# multiplexor.net
KiCad netlist of a schematic drawn in EAGLE
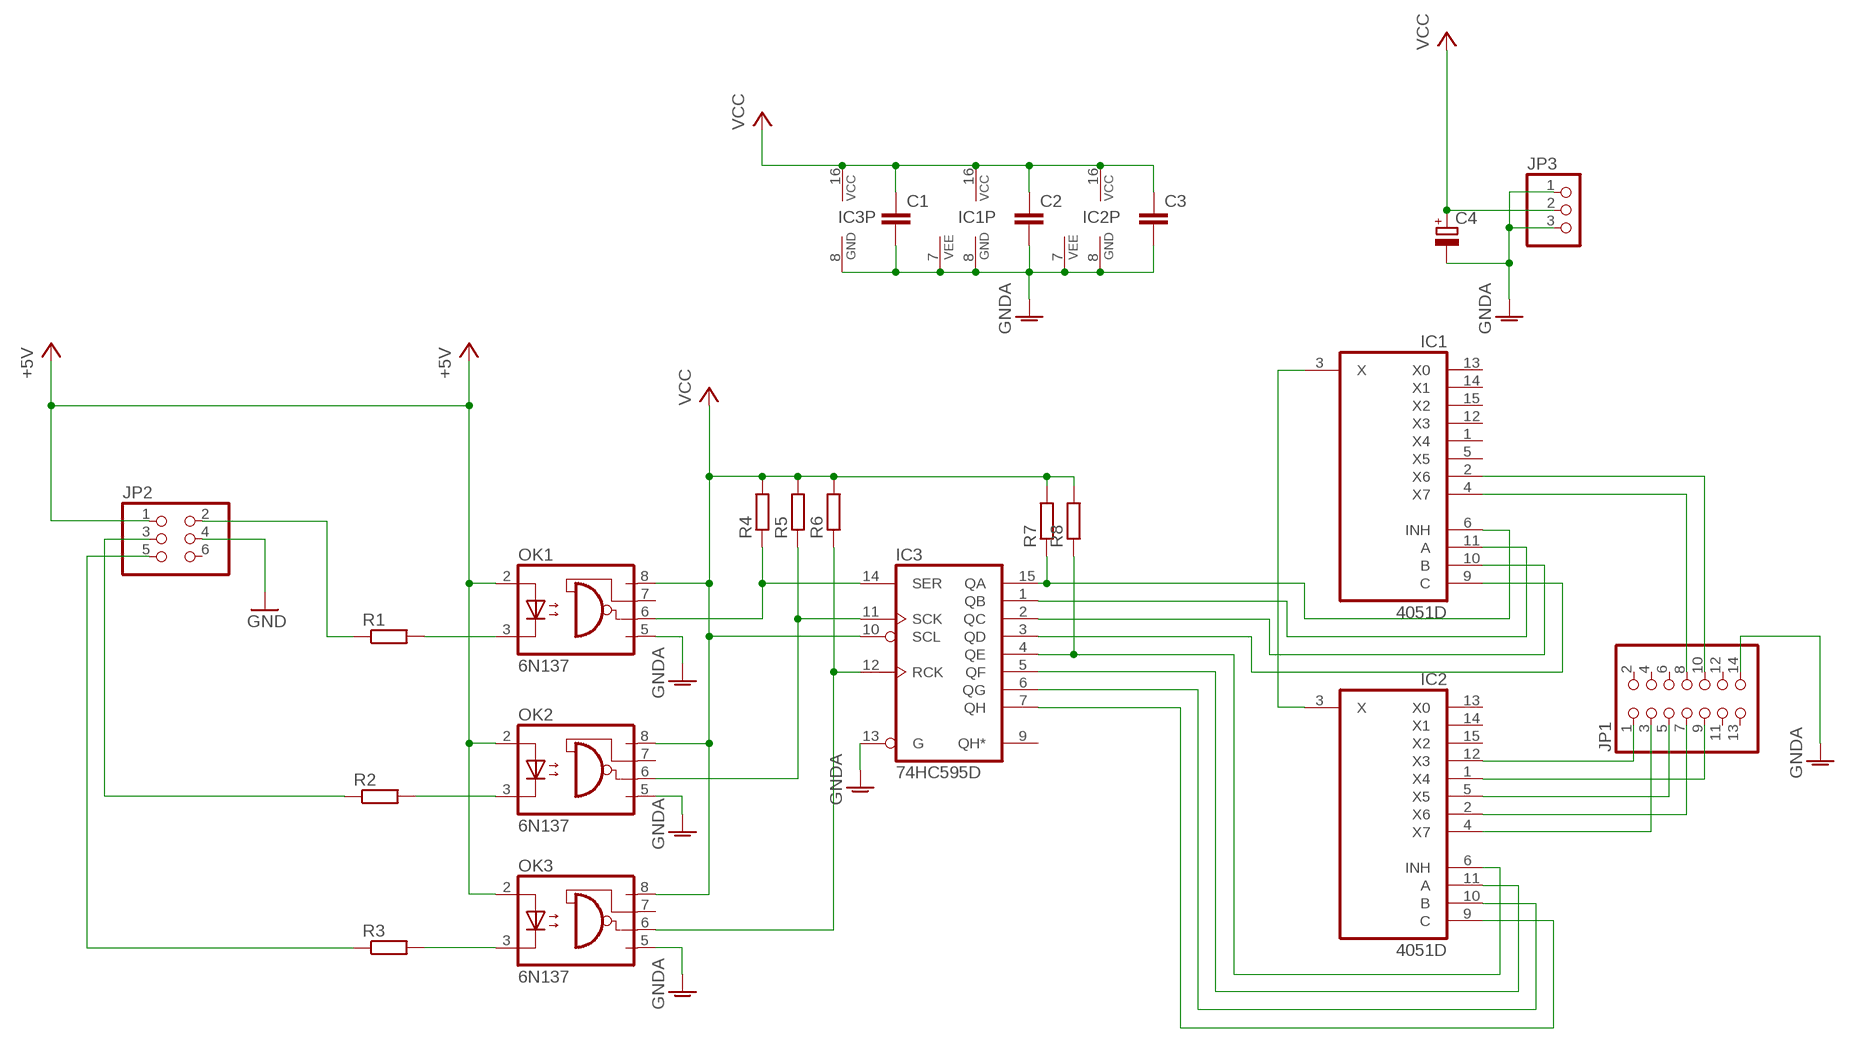
[diagram p0: schematic, sheet 1]

(export (version "E")
  (design (tool "Eeschema 10.0.6"))
  (components
    (comp (ref "C1")
      (value "C-EUC1206K")
      (footprint "eagle-import:C1206K")
      (libsource (lib "eagle-import") (part "C-EUC1206K"))
    )
    (comp (ref "C2")
      (value "C-EUC1206K")
      (footprint "eagle-import:C1206K")
      (libsource (lib "eagle-import") (part "C-EUC1206K"))
    )
    (comp (ref "C3")
      (value "C-EUC1206K")
      (footprint "eagle-import:C1206K")
      (libsource (lib "eagle-import") (part "C-EUC1206K"))
    )
    (comp (ref "C4")
      (value "CPOL-EUE2.5-6")
      (footprint "eagle-import:E2,5-6")
      (libsource (lib "eagle-import") (part "CPOL-EUE2.5-6"))
    )
    (comp (ref "IC1")
      (value "4051D")
      (footprint "eagle-import:SO16")
      (libsource (lib "eagle-import") (part "4051D"))
    )
    (comp (ref "IC2")
      (value "4051D")
      (footprint "eagle-import:SO16")
      (libsource (lib "eagle-import") (part "4051D"))
    )
    (comp (ref "IC3")
      (value "74HC595D")
      (footprint "eagle-import:SO16")
      (libsource (lib "eagle-import") (part "74595DHC"))
    )
    (comp (ref "JP1")
      (value "PINHD-2X7")
      (footprint "eagle-import:2X07")
      (libsource (lib "eagle-import") (part "PINHD-2X7"))
    )
    (comp (ref "JP2")
      (value "PINHD-2X3")
      (footprint "eagle-import:2X03")
      (libsource (lib "eagle-import") (part "PINHD-2X3"))
    )
    (comp (ref "JP3")
      (value "PINHD-1X3")
      (footprint "eagle-import:1X03")
      (libsource (lib "eagle-import") (part "PINHD-1X3"))
    )
    (comp (ref "OK1")
      (value "6N137")
      (footprint "eagle-import:DIL08")
      (libsource (lib "eagle-import") (part "6N137"))
    )
    (comp (ref "OK2")
      (value "6N137")
      (footprint "eagle-import:DIL08")
      (libsource (lib "eagle-import") (part "6N137"))
    )
    (comp (ref "OK3")
      (value "6N137")
      (footprint "eagle-import:DIL08")
      (libsource (lib "eagle-import") (part "6N137"))
    )
    (comp (ref "R1")
      (value "R-EU_R1206")
      (footprint "eagle-import:R1206")
      (libsource (lib "eagle-import") (part "R-EU_R1206"))
    )
    (comp (ref "R2")
      (value "R-EU_R1206")
      (footprint "eagle-import:R1206")
      (libsource (lib "eagle-import") (part "R-EU_R1206"))
    )
    (comp (ref "R3")
      (value "R-EU_R1206")
      (footprint "eagle-import:R1206")
      (libsource (lib "eagle-import") (part "R-EU_R1206"))
    )
    (comp (ref "R4")
      (value "R-EU_R1206")
      (footprint "eagle-import:R1206")
      (libsource (lib "eagle-import") (part "R-EU_R1206"))
    )
    (comp (ref "R5")
      (value "R-EU_R1206")
      (footprint "eagle-import:R1206")
      (libsource (lib "eagle-import") (part "R-EU_R1206"))
    )
    (comp (ref "R6")
      (value "R-EU_R1206")
      (footprint "eagle-import:R1206")
      (libsource (lib "eagle-import") (part "R-EU_R1206"))
    )
    (comp (ref "R7")
      (value "R-EU_R1206")
      (footprint "eagle-import:R1206")
      (libsource (lib "eagle-import") (part "R-EU_R1206"))
    )
    (comp (ref "R8")
      (value "R-EU_R1206")
      (footprint "eagle-import:R1206")
      (libsource (lib "eagle-import") (part "R-EU_R1206"))
    )
  )
  (nets
    (net (code "1") (name "+5V") (class "Default")
      (node (ref "JP2") (pin "1") (pinfunction "1_1") (pintype "passive"))
      (node (ref "OK1") (pin "2") (pinfunction "A_2") (pintype "passive"))
      (node (ref "OK2") (pin "2") (pinfunction "A_2") (pintype "passive"))
      (node (ref "OK3") (pin "2") (pinfunction "A_2") (pintype "passive"))
    )
    (net (code "2") (name "GND") (class "Default")
      (node (ref "JP2") (pin "4") (pinfunction "4_4") (pintype "passive"))
    )
    (net (code "3") (name "GNDA") (class "Default")
      (node (ref "C1") (pin "2") (pinfunction "2_2") (pintype "passive"))
      (node (ref "C2") (pin "2") (pinfunction "2_2") (pintype "passive"))
      (node (ref "C3") (pin "2") (pinfunction "2_2") (pintype "passive"))
      (node (ref "C4") (pin "-") (pinfunction "-_-") (pintype "passive"))
      (node (ref "IC1") (pin "7") (pinfunction "VEE_7") (pintype "power_in"))
      (node (ref "IC1") (pin "8") (pinfunction "GND_8") (pintype "power_in"))
      (node (ref "IC2") (pin "7") (pinfunction "VEE_7") (pintype "power_in"))
      (node (ref "IC2") (pin "8") (pinfunction "GND_8") (pintype "power_in"))
      (node (ref "IC3") (pin "13") (pinfunction "G_13") (pintype "input"))
      (node (ref "IC3") (pin "8") (pinfunction "GND_8") (pintype "power_in"))
      (node (ref "JP1") (pin "14") (pinfunction "14_14") (pintype "passive"))
      (node (ref "JP3") (pin "1") (pinfunction "1_1") (pintype "passive"))
      (node (ref "JP3") (pin "3") (pinfunction "3_3") (pintype "passive"))
      (node (ref "OK1") (pin "5") (pinfunction "GND_5") (pintype "passive"))
      (node (ref "OK2") (pin "5") (pinfunction "GND_5") (pintype "passive"))
      (node (ref "OK3") (pin "5") (pinfunction "GND_5") (pintype "passive"))
    )
    (net (code "4") (name "Net-(IC1A-A)") (class "Default")
      (node (ref "IC1") (pin "11") (pinfunction "A_11") (pintype "input"))
      (node (ref "IC3") (pin "1") (pinfunction "QB_1") (pintype "tri_state"))
    )
    (net (code "5") (name "Net-(IC1A-B)") (class "Default")
      (node (ref "IC1") (pin "10") (pinfunction "B_10") (pintype "input"))
      (node (ref "IC3") (pin "2") (pinfunction "QC_2") (pintype "tri_state"))
    )
    (net (code "6") (name "Net-(IC1A-C)") (class "Default")
      (node (ref "IC1") (pin "9") (pinfunction "C_9") (pintype "input"))
      (node (ref "IC3") (pin "3") (pinfunction "QD_3") (pintype "tri_state"))
    )
    (net (code "7") (name "Net-(IC1A-INH)") (class "Default")
      (node (ref "IC1") (pin "6") (pinfunction "INH_6") (pintype "input"))
      (node (ref "IC3") (pin "15") (pinfunction "QA_15") (pintype "tri_state"))
      (node (ref "R7") (pin "1") (pinfunction "1_1") (pintype "passive"))
    )
    (net (code "8") (name "Net-(IC1A-X)") (class "Default")
      (node (ref "IC1") (pin "3") (pinfunction "X_3") (pintype "bidirectional"))
      (node (ref "IC2") (pin "3") (pinfunction "X_3") (pintype "bidirectional"))
    )
    (net (code "9") (name "Net-(IC1A-X6)") (class "Default")
      (node (ref "IC1") (pin "2") (pinfunction "X6_2") (pintype "bidirectional"))
      (node (ref "JP1") (pin "10") (pinfunction "10_10") (pintype "passive"))
    )
    (net (code "10") (name "Net-(IC1A-X7)") (class "Default")
      (node (ref "IC1") (pin "4") (pinfunction "X7_4") (pintype "bidirectional"))
      (node (ref "JP1") (pin "8") (pinfunction "8_8") (pintype "passive"))
    )
    (net (code "11") (name "Net-(IC2A-A)") (class "Default")
      (node (ref "IC2") (pin "11") (pinfunction "A_11") (pintype "input"))
      (node (ref "IC3") (pin "5") (pinfunction "QF_5") (pintype "tri_state"))
    )
    (net (code "12") (name "Net-(IC2A-B)") (class "Default")
      (node (ref "IC2") (pin "10") (pinfunction "B_10") (pintype "input"))
      (node (ref "IC3") (pin "6") (pinfunction "QG_6") (pintype "tri_state"))
    )
    (net (code "13") (name "Net-(IC2A-C)") (class "Default")
      (node (ref "IC2") (pin "9") (pinfunction "C_9") (pintype "input"))
      (node (ref "IC3") (pin "7") (pinfunction "QH_7") (pintype "tri_state"))
    )
    (net (code "14") (name "Net-(IC2A-INH)") (class "Default")
      (node (ref "IC2") (pin "6") (pinfunction "INH_6") (pintype "input"))
      (node (ref "IC3") (pin "4") (pinfunction "QE_4") (pintype "tri_state"))
      (node (ref "R8") (pin "1") (pinfunction "1_1") (pintype "passive"))
    )
    (net (code "15") (name "Net-(IC2A-X3)") (class "Default")
      (node (ref "IC2") (pin "12") (pinfunction "X3_12") (pintype "bidirectional"))
      (node (ref "JP1") (pin "1") (pinfunction "1_1") (pintype "passive"))
    )
    (net (code "16") (name "Net-(IC2A-X4)") (class "Default")
      (node (ref "IC2") (pin "1") (pinfunction "X4_1") (pintype "bidirectional"))
      (node (ref "JP1") (pin "9") (pinfunction "9_9") (pintype "passive"))
    )
    (net (code "17") (name "Net-(IC2A-X5)") (class "Default")
      (node (ref "IC2") (pin "5") (pinfunction "X5_5") (pintype "bidirectional"))
      (node (ref "JP1") (pin "5") (pinfunction "5_5") (pintype "passive"))
    )
    (net (code "18") (name "Net-(IC2A-X6)") (class "Default")
      (node (ref "IC2") (pin "2") (pinfunction "X6_2") (pintype "bidirectional"))
      (node (ref "JP1") (pin "7") (pinfunction "7_7") (pintype "passive"))
    )
    (net (code "19") (name "Net-(IC2A-X7)") (class "Default")
      (node (ref "IC2") (pin "4") (pinfunction "X7_4") (pintype "bidirectional"))
      (node (ref "JP1") (pin "3") (pinfunction "3_3") (pintype "passive"))
    )
    (net (code "20") (name "Net-(IC3A-RCK)") (class "Default")
      (node (ref "IC3") (pin "12") (pinfunction "RCK_12") (pintype "input"))
      (node (ref "OK3") (pin "6") (pinfunction "VO_6") (pintype "passive"))
      (node (ref "R6") (pin "1") (pinfunction "1_1") (pintype "passive"))
    )
    (net (code "21") (name "Net-(IC3A-SCK)") (class "Default")
      (node (ref "IC3") (pin "11") (pinfunction "SCK_11") (pintype "input"))
      (node (ref "OK2") (pin "6") (pinfunction "VO_6") (pintype "passive"))
      (node (ref "R5") (pin "1") (pinfunction "1_1") (pintype "passive"))
    )
    (net (code "22") (name "Net-(IC3A-SER)") (class "Default")
      (node (ref "IC3") (pin "14") (pinfunction "SER_14") (pintype "input"))
      (node (ref "OK1") (pin "6") (pinfunction "VO_6") (pintype "passive"))
      (node (ref "R4") (pin "1") (pinfunction "1_1") (pintype "passive"))
    )
    (net (code "23") (name "Net-(JP2-Pad2)") (class "Default")
      (node (ref "JP2") (pin "2") (pinfunction "2_2") (pintype "passive"))
      (node (ref "R1") (pin "1") (pinfunction "1_1") (pintype "passive"))
    )
    (net (code "24") (name "Net-(JP2-Pad3)") (class "Default")
      (node (ref "JP2") (pin "3") (pinfunction "3_3") (pintype "passive"))
      (node (ref "R2") (pin "1") (pinfunction "1_1") (pintype "passive"))
    )
    (net (code "25") (name "Net-(JP2-Pad5)") (class "Default")
      (node (ref "JP2") (pin "5") (pinfunction "5_5") (pintype "passive"))
      (node (ref "R3") (pin "1") (pinfunction "1_1") (pintype "passive"))
    )
    (net (code "26") (name "Net-(OK1-C)") (class "Default")
      (node (ref "OK1") (pin "3") (pinfunction "C_3") (pintype "passive"))
      (node (ref "R1") (pin "2") (pinfunction "2_2") (pintype "passive"))
    )
    (net (code "27") (name "Net-(OK2-C)") (class "Default")
      (node (ref "OK2") (pin "3") (pinfunction "C_3") (pintype "passive"))
      (node (ref "R2") (pin "2") (pinfunction "2_2") (pintype "passive"))
    )
    (net (code "28") (name "Net-(OK3-C)") (class "Default")
      (node (ref "OK3") (pin "3") (pinfunction "C_3") (pintype "passive"))
      (node (ref "R3") (pin "2") (pinfunction "2_2") (pintype "passive"))
    )
    (net (code "29") (name "VCC") (class "Default")
      (node (ref "C1") (pin "1") (pinfunction "1_1") (pintype "passive"))
      (node (ref "C2") (pin "1") (pinfunction "1_1") (pintype "passive"))
      (node (ref "C3") (pin "1") (pinfunction "1_1") (pintype "passive"))
      (node (ref "C4") (pin "+") (pinfunction "+_+") (pintype "passive"))
      (node (ref "IC1") (pin "16") (pinfunction "VCC_16") (pintype "power_in"))
      (node (ref "IC2") (pin "16") (pinfunction "VCC_16") (pintype "power_in"))
      (node (ref "IC3") (pin "10") (pinfunction "SCL_10") (pintype "input"))
      (node (ref "IC3") (pin "16") (pinfunction "VCC_16") (pintype "power_in"))
      (node (ref "JP3") (pin "2") (pinfunction "2_2") (pintype "passive"))
      (node (ref "OK1") (pin "8") (pinfunction "VCC_8") (pintype "passive"))
      (node (ref "OK2") (pin "8") (pinfunction "VCC_8") (pintype "passive"))
      (node (ref "OK3") (pin "8") (pinfunction "VCC_8") (pintype "passive"))
      (node (ref "R4") (pin "2") (pinfunction "2_2") (pintype "passive"))
      (node (ref "R5") (pin "2") (pinfunction "2_2") (pintype "passive"))
      (node (ref "R6") (pin "2") (pinfunction "2_2") (pintype "passive"))
      (node (ref "R7") (pin "2") (pinfunction "2_2") (pintype "passive"))
      (node (ref "R8") (pin "2") (pinfunction "2_2") (pintype "passive"))
    )
    (net (code "30") (name "unconnected-(IC1A-X0-Pad13)") (class "Default")
      (node (ref "IC1") (pin "13") (pinfunction "X0_13") (pintype "bidirectional"))
    )
    (net (code "31") (name "unconnected-(IC1A-X1-Pad14)") (class "Default")
      (node (ref "IC1") (pin "14") (pinfunction "X1_14") (pintype "bidirectional"))
    )
    (net (code "32") (name "unconnected-(IC1A-X2-Pad15)") (class "Default")
      (node (ref "IC1") (pin "15") (pinfunction "X2_15") (pintype "bidirectional"))
    )
    (net (code "33") (name "unconnected-(IC1A-X3-Pad12)") (class "Default")
      (node (ref "IC1") (pin "12") (pinfunction "X3_12") (pintype "bidirectional"))
    )
    (net (code "34") (name "unconnected-(IC1A-X4-Pad1)") (class "Default")
      (node (ref "IC1") (pin "1") (pinfunction "X4_1") (pintype "bidirectional"))
    )
    (net (code "35") (name "unconnected-(IC1A-X5-Pad5)") (class "Default")
      (node (ref "IC1") (pin "5") (pinfunction "X5_5") (pintype "bidirectional"))
    )
    (net (code "36") (name "unconnected-(IC2A-X0-Pad13)") (class "Default")
      (node (ref "IC2") (pin "13") (pinfunction "X0_13") (pintype "bidirectional"))
    )
    (net (code "37") (name "unconnected-(IC2A-X1-Pad14)") (class "Default")
      (node (ref "IC2") (pin "14") (pinfunction "X1_14") (pintype "bidirectional"))
    )
    (net (code "38") (name "unconnected-(IC2A-X2-Pad15)") (class "Default")
      (node (ref "IC2") (pin "15") (pinfunction "X2_15") (pintype "bidirectional"))
    )
    (net (code "39") (name "unconnected-(IC3A-QH*-Pad9)") (class "Default")
      (node (ref "IC3") (pin "9") (pinfunction "QH*_9") (pintype "tri_state"))
    )
    (net (code "40") (name "unconnected-(JP1-Pad2)") (class "Default")
      (node (ref "JP1") (pin "2") (pinfunction "2_2") (pintype "passive"))
    )
    (net (code "41") (name "unconnected-(JP1-Pad4)") (class "Default")
      (node (ref "JP1") (pin "4") (pinfunction "4_4") (pintype "passive"))
    )
    (net (code "42") (name "unconnected-(JP1-Pad6)") (class "Default")
      (node (ref "JP1") (pin "6") (pinfunction "6_6") (pintype "passive"))
    )
    (net (code "43") (name "unconnected-(JP1-Pad11)") (class "Default")
      (node (ref "JP1") (pin "11") (pinfunction "11_11") (pintype "passive"))
    )
    (net (code "44") (name "unconnected-(JP1-Pad12)") (class "Default")
      (node (ref "JP1") (pin "12") (pinfunction "12_12") (pintype "passive"))
    )
    (net (code "45") (name "unconnected-(JP1-Pad13)") (class "Default")
      (node (ref "JP1") (pin "13") (pinfunction "13_13") (pintype "passive"))
    )
    (net (code "46") (name "unconnected-(JP2-Pad6)") (class "Default")
      (node (ref "JP2") (pin "6") (pinfunction "6_6") (pintype "passive"))
    )
    (net (code "47") (name "unconnected-(OK1-VE-Pad7)") (class "Default")
      (node (ref "OK1") (pin "7") (pinfunction "VE_7") (pintype "passive"))
    )
    (net (code "48") (name "unconnected-(OK2-VE-Pad7)") (class "Default")
      (node (ref "OK2") (pin "7") (pinfunction "VE_7") (pintype "passive"))
    )
    (net (code "49") (name "unconnected-(OK3-VE-Pad7)") (class "Default")
      (node (ref "OK3") (pin "7") (pinfunction "VE_7") (pintype "passive"))
    )
  )
)
